# gesamt.net
KiCad netlist of a schematic drawn in EAGLE
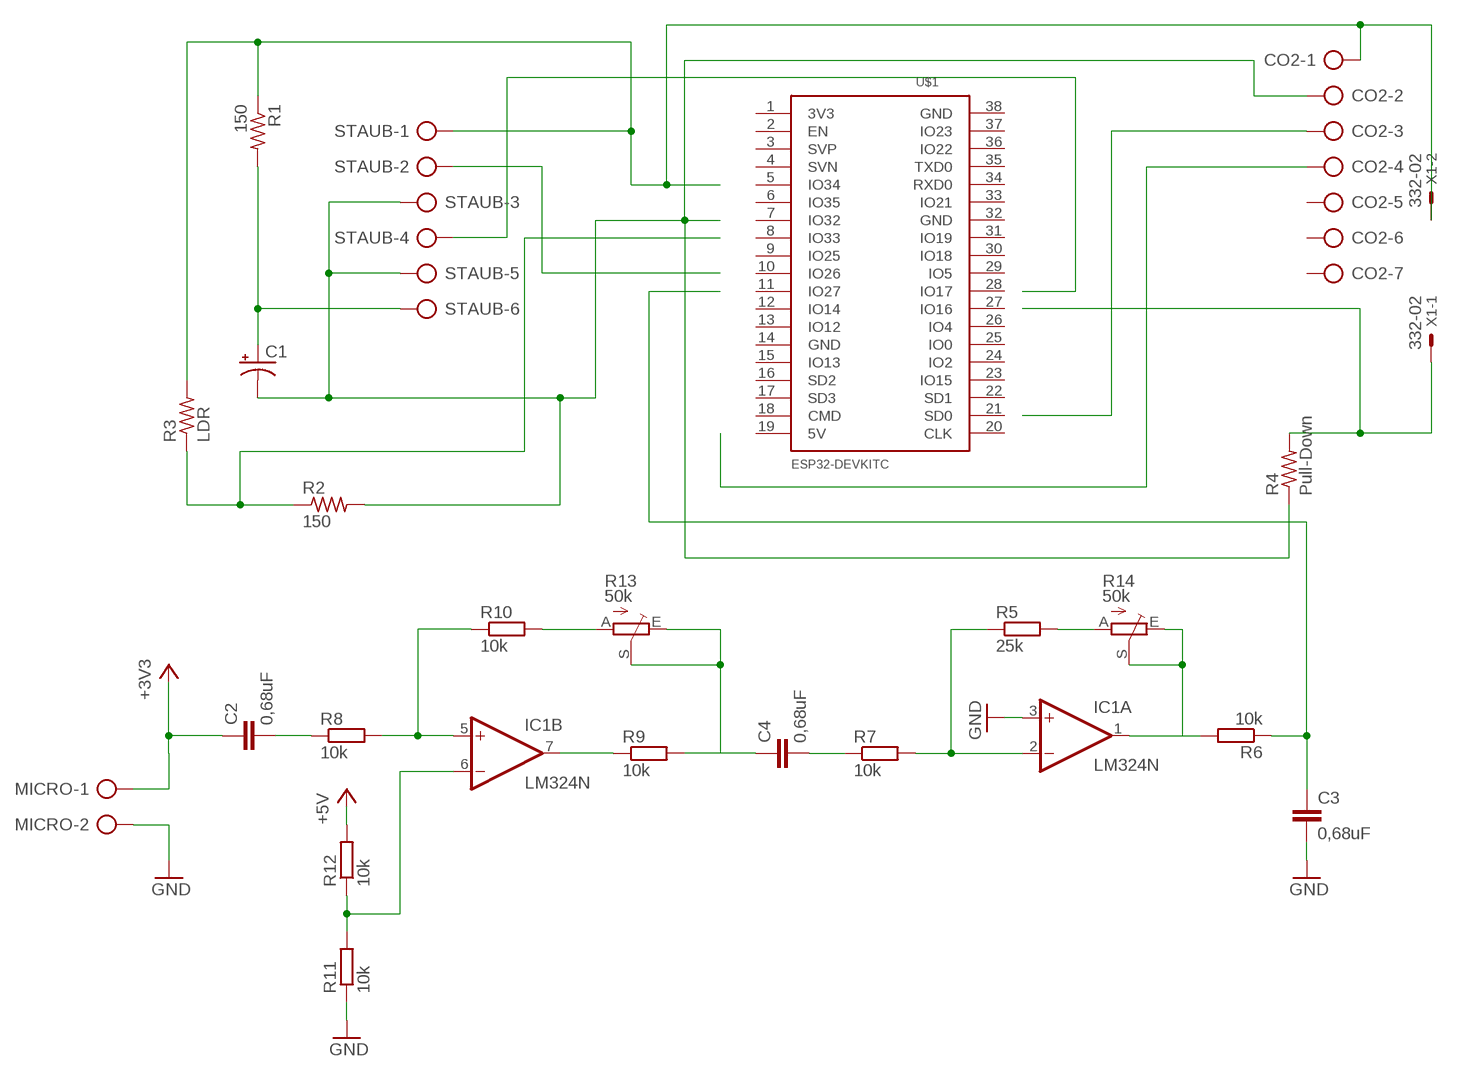
[diagram p0: schematic, sheet 1]

(export (version "E")
  (design (tool "Eeschema 10.0.6"))
  (components
    (comp (ref "C1")
      (value "CPOL-USE2,5-6E")
      (footprint "eagle-import:E2,5-6E")
      (libsource (lib "eagle-import") (part "CPOL-USE2,5-6E"))
    )
    (comp (ref "C2")
      (value "0,68uF")
      (footprint "eagle-import:C025-025X050")
      (libsource (lib "eagle-import") (part "C-EU025-025X050"))
    )
    (comp (ref "C3")
      (value "0,68uF")
      (footprint "eagle-import:C025-025X050")
      (libsource (lib "eagle-import") (part "C-EU025-025X050"))
    )
    (comp (ref "C4")
      (value "0,68uF")
      (footprint "eagle-import:C025-025X050")
      (libsource (lib "eagle-import") (part "C-EU025-025X050"))
    )
    (comp (ref "CO2")
      (value "AK300/7")
      (footprint "eagle-import:AK300_7")
      (libsource (lib "eagle-import") (part "AK300/7"))
    )
    (comp (ref "IC1")
      (value "LM324N")
      (footprint "eagle-import:DIL14")
      (libsource (lib "eagle-import") (part "LM324N"))
    )
    (comp (ref "MICRO")
      (value "AK300/2")
      (footprint "eagle-import:AK300_2")
      (libsource (lib "eagle-import") (part "AK300/2"))
    )
    (comp (ref "R1")
      (value "150")
      (footprint "eagle-import:0207_10")
      (libsource (lib "eagle-import") (part "R-US_0207/10"))
    )
    (comp (ref "R2")
      (value "150")
      (footprint "eagle-import:0207_10")
      (libsource (lib "eagle-import") (part "R-US_0207/10"))
    )
    (comp (ref "R3")
      (value "LDR")
      (footprint "eagle-import:V234_12")
      (libsource (lib "eagle-import") (part "R-US_V234/12"))
    )
    (comp (ref "R4")
      (value "Pull-Down")
      (footprint "eagle-import:0207_10")
      (libsource (lib "eagle-import") (part "R-US_0207/10"))
    )
    (comp (ref "R5")
      (value "25k")
      (footprint "eagle-import:0204_7")
      (libsource (lib "eagle-import") (part "R-EU_0204/7"))
    )
    (comp (ref "R6")
      (value "10k")
      (footprint "eagle-import:0204_7")
      (libsource (lib "eagle-import") (part "R-EU_0204/7"))
    )
    (comp (ref "R7")
      (value "10k")
      (footprint "eagle-import:0204_7")
      (libsource (lib "eagle-import") (part "R-EU_0204/7"))
    )
    (comp (ref "R8")
      (value "10k")
      (footprint "eagle-import:0204_7")
      (libsource (lib "eagle-import") (part "R-EU_0204/7"))
    )
    (comp (ref "R9")
      (value "10k")
      (footprint "eagle-import:0204_7")
      (libsource (lib "eagle-import") (part "R-EU_0204/7"))
    )
    (comp (ref "R10")
      (value "10k")
      (footprint "eagle-import:0204_7")
      (libsource (lib "eagle-import") (part "R-EU_0204/7"))
    )
    (comp (ref "R11")
      (value "10k")
      (footprint "eagle-import:0204_7")
      (libsource (lib "eagle-import") (part "R-EU_0204/7"))
    )
    (comp (ref "R12")
      (value "10k")
      (footprint "eagle-import:0204_7")
      (libsource (lib "eagle-import") (part "R-EU_0204/7"))
    )
    (comp (ref "R13")
      (value "50k")
      (footprint "eagle-import:LI10")
      (libsource (lib "eagle-import") (part "TRIM_EU-LI10"))
    )
    (comp (ref "R14")
      (value "50k")
      (footprint "eagle-import:LI10")
      (libsource (lib "eagle-import") (part "TRIM_EU-LI10"))
    )
    (comp (ref "STAUB")
      (value "AK300/6")
      (footprint "eagle-import:AK300_6")
      (libsource (lib "eagle-import") (part "AK300/6"))
    )
    (comp (ref "U$1")
      (value "ESP32DEVKITC")
      (footprint "eagle-import:ESP32-DEVKITC")
      (libsource (lib "eagle-import") (part "ESP32DEVKITC"))
    )
    (comp (ref "X1")
      (value "332-02")
      (footprint "eagle-import:332-02")
      (libsource (lib "eagle-import") (part "332-02"))
    )
  )
  (nets
    (net (code "1") (name "+3V3") (class "Default")
      (node (ref "C2") (pin "1") (pinfunction "1_1") (pintype "passive"))
      (node (ref "MICRO") (pin "1") (pinfunction "KL_1") (pintype "passive"))
    )
    (net (code "2") (name "+5V") (class "Default")
      (node (ref "R12") (pin "2") (pinfunction "2_2") (pintype "passive"))
    )
    (net (code "3") (name "GND") (class "Default")
      (node (ref "C3") (pin "2") (pinfunction "2_2") (pintype "passive"))
      (node (ref "IC1") (pin "3") (pinfunction "+IN_3") (pintype "input"))
      (node (ref "MICRO") (pin "2") (pinfunction "KL_2") (pintype "passive"))
      (node (ref "R11") (pin "1") (pinfunction "1_1") (pintype "passive"))
    )
    (net (code "4") (name "Net-(C2-Pad2)") (class "Default")
      (node (ref "C2") (pin "2") (pinfunction "2_2") (pintype "passive"))
      (node (ref "R8") (pin "1") (pinfunction "1_1") (pintype "passive"))
    )
    (net (code "5") (name "Net-(C3-Pad1)") (class "Default")
      (node (ref "C3") (pin "1") (pinfunction "1_1") (pintype "passive"))
      (node (ref "R6") (pin "1") (pinfunction "1_1") (pintype "passive"))
    )
    (net (code "6") (name "Net-(C4-Pad1)") (class "Default")
      (node (ref "C4") (pin "1") (pinfunction "1_1") (pintype "passive"))
      (node (ref "R13") (pin "E") (pinfunction "E_E") (pintype "passive"))
      (node (ref "R13") (pin "S") (pinfunction "S_S") (pintype "passive"))
      (node (ref "R9") (pin "2") (pinfunction "2_2") (pintype "passive"))
    )
    (net (code "7") (name "Net-(C4-Pad2)") (class "Default")
      (node (ref "C4") (pin "2") (pinfunction "2_2") (pintype "passive"))
      (node (ref "R7") (pin "1") (pinfunction "1_1") (pintype "passive"))
    )
    (net (code "8") (name "Net-(CO2A-KL)") (class "Default")
      (node (ref "CO2") (pin "1") (pinfunction "KL_1") (pintype "passive"))
      (node (ref "R1") (pin "1") (pinfunction "1_1") (pintype "passive"))
      (node (ref "R3") (pin "2") (pinfunction "2_2") (pintype "passive"))
      (node (ref "STAUB") (pin "1") (pinfunction "KL_1") (pintype "passive"))
      (node (ref "X1") (pin "2") (pinfunction "S_2") (pintype "passive"))
    )
    (net (code "9") (name "Net-(CO2B-KL)") (class "Default")
      (node (ref "C1") (pin "-") (pinfunction "-_-") (pintype "passive"))
      (node (ref "CO2") (pin "2") (pinfunction "KL_2") (pintype "passive"))
      (node (ref "R2") (pin "2") (pinfunction "2_2") (pintype "passive"))
      (node (ref "R4") (pin "1") (pinfunction "1_1") (pintype "passive"))
      (node (ref "STAUB") (pin "3") (pinfunction "KL_3") (pintype "passive"))
      (node (ref "STAUB") (pin "5") (pinfunction "KL_5") (pintype "passive"))
    )
    (net (code "10") (name "Net-(IC1A--IN)") (class "Default")
      (node (ref "IC1") (pin "2") (pinfunction "-IN_2") (pintype "input"))
      (node (ref "R5") (pin "1") (pinfunction "1_1") (pintype "passive"))
      (node (ref "R7") (pin "2") (pinfunction "2_2") (pintype "passive"))
    )
    (net (code "11") (name "Net-(IC1A-OUT)") (class "Default")
      (node (ref "IC1") (pin "1") (pinfunction "OUT_1") (pintype "output"))
      (node (ref "R14") (pin "E") (pinfunction "E_E") (pintype "passive"))
      (node (ref "R14") (pin "S") (pinfunction "S_S") (pintype "passive"))
      (node (ref "R6") (pin "2") (pinfunction "2_2") (pintype "passive"))
    )
    (net (code "12") (name "Net-(IC1B-+IN)") (class "Default")
      (node (ref "IC1") (pin "5") (pinfunction "+IN_5") (pintype "input"))
      (node (ref "R10") (pin "1") (pinfunction "1_1") (pintype "passive"))
      (node (ref "R8") (pin "2") (pinfunction "2_2") (pintype "passive"))
    )
    (net (code "13") (name "Net-(IC1B--IN)") (class "Default")
      (node (ref "IC1") (pin "6") (pinfunction "-IN_6") (pintype "input"))
      (node (ref "R11") (pin "2") (pinfunction "2_2") (pintype "passive"))
      (node (ref "R12") (pin "1") (pinfunction "1_1") (pintype "passive"))
    )
    (net (code "14") (name "Net-(IC1B-OUT)") (class "Default")
      (node (ref "IC1") (pin "7") (pinfunction "OUT_7") (pintype "output"))
      (node (ref "R9") (pin "1") (pinfunction "1_1") (pintype "passive"))
    )
    (net (code "15") (name "Net-(R2-Pad1)") (class "Default")
      (node (ref "R2") (pin "1") (pinfunction "1_1") (pintype "passive"))
      (node (ref "R3") (pin "1") (pinfunction "1_1") (pintype "passive"))
    )
    (net (code "16") (name "Net-(R10-Pad2)") (class "Default")
      (node (ref "R10") (pin "2") (pinfunction "2_2") (pintype "passive"))
      (node (ref "R13") (pin "A") (pinfunction "A_A") (pintype "passive"))
    )
    (net (code "17") (name "Net-(R14-PadA)") (class "Default")
      (node (ref "R14") (pin "A") (pinfunction "A_A") (pintype "passive"))
      (node (ref "R5") (pin "2") (pinfunction "2_2") (pintype "passive"))
    )
    (net (code "18") (name "Net-(STAUBF-KL)") (class "Default")
      (node (ref "C1") (pin "+") (pinfunction "+_+") (pintype "passive"))
      (node (ref "R1") (pin "2") (pinfunction "2_2") (pintype "passive"))
      (node (ref "STAUB") (pin "6") (pinfunction "KL_6") (pintype "passive"))
    )
    (net (code "19") (name "Net-(X1A-S)") (class "Default")
      (node (ref "R4") (pin "2") (pinfunction "2_2") (pintype "passive"))
      (node (ref "X1") (pin "1") (pinfunction "S_1") (pintype "passive"))
    )
    (net (code "20") (name "unconnected-(CO2C-KL-Pad3)") (class "Default")
      (node (ref "CO2") (pin "3") (pinfunction "KL_3") (pintype "passive"))
    )
    (net (code "21") (name "unconnected-(CO2D-KL-Pad4)") (class "Default")
      (node (ref "CO2") (pin "4") (pinfunction "KL_4") (pintype "passive"))
    )
    (net (code "22") (name "unconnected-(CO2E-KL-Pad5)") (class "Default")
      (node (ref "CO2") (pin "5") (pinfunction "KL_5") (pintype "passive"))
    )
    (net (code "23") (name "unconnected-(CO2F-KL-Pad6)") (class "Default")
      (node (ref "CO2") (pin "6") (pinfunction "KL_6") (pintype "passive"))
    )
    (net (code "24") (name "unconnected-(CO2G-KL-Pad7)") (class "Default")
      (node (ref "CO2") (pin "7") (pinfunction "KL_7") (pintype "passive"))
    )
    (net (code "25") (name "unconnected-(STAUBB-KL-Pad2)") (class "Default")
      (node (ref "STAUB") (pin "2") (pinfunction "KL_2") (pintype "passive"))
    )
    (net (code "26") (name "unconnected-(STAUBD-KL-Pad4)") (class "Default")
      (node (ref "STAUB") (pin "4") (pinfunction "KL_4") (pintype "passive"))
    )
    (net (code "27") (name "unconnected-(U$1-3V3-Pad1)") (class "Default")
      (node (ref "U$1") (pin "1") (pinfunction "3V3_1") (pintype "bidirectional"))
    )
    (net (code "28") (name "unconnected-(U$1-5V-Pad19)") (class "Default")
      (node (ref "U$1") (pin "19") (pinfunction "5V_19") (pintype "bidirectional"))
    )
    (net (code "29") (name "unconnected-(U$1-CLK-Pad20)") (class "Default")
      (node (ref "U$1") (pin "20") (pinfunction "CLK_20") (pintype "bidirectional"))
    )
    (net (code "30") (name "unconnected-(U$1-CMD-Pad18)") (class "Default")
      (node (ref "U$1") (pin "18") (pinfunction "CMD_18") (pintype "bidirectional"))
    )
    (net (code "31") (name "unconnected-(U$1-EN-Pad2)") (class "Default")
      (node (ref "U$1") (pin "2") (pinfunction "EN_2") (pintype "bidirectional"))
    )
    (net (code "32") (name "unconnected-(U$1-GND-Pad14)") (class "Default")
      (node (ref "U$1") (pin "14") (pinfunction "GND_14") (pintype "bidirectional"))
    )
    (net (code "33") (name "unconnected-(U$1-GND-Pad32)") (class "Default")
      (node (ref "U$1") (pin "32") (pinfunction "GND_32") (pintype "bidirectional"))
    )
    (net (code "34") (name "unconnected-(U$1-GND-Pad38)") (class "Default")
      (node (ref "U$1") (pin "38") (pinfunction "GND_38") (pintype "bidirectional"))
    )
    (net (code "35") (name "unconnected-(U$1-IO0-Pad25)") (class "Default")
      (node (ref "U$1") (pin "25") (pinfunction "IO0_25") (pintype "bidirectional"))
    )
    (net (code "36") (name "unconnected-(U$1-IO2-Pad24)") (class "Default")
      (node (ref "U$1") (pin "24") (pinfunction "IO2_24") (pintype "bidirectional"))
    )
    (net (code "37") (name "unconnected-(U$1-IO4-Pad26)") (class "Default")
      (node (ref "U$1") (pin "26") (pinfunction "IO4_26") (pintype "bidirectional"))
    )
    (net (code "38") (name "unconnected-(U$1-IO5-Pad29)") (class "Default")
      (node (ref "U$1") (pin "29") (pinfunction "IO5_29") (pintype "bidirectional"))
    )
    (net (code "39") (name "unconnected-(U$1-IO12-Pad13)") (class "Default")
      (node (ref "U$1") (pin "13") (pinfunction "IO12_13") (pintype "bidirectional"))
    )
    (net (code "40") (name "unconnected-(U$1-IO13-Pad15)") (class "Default")
      (node (ref "U$1") (pin "15") (pinfunction "IO13_15") (pintype "bidirectional"))
    )
    (net (code "41") (name "unconnected-(U$1-IO14-Pad12)") (class "Default")
      (node (ref "U$1") (pin "12") (pinfunction "IO14_12") (pintype "bidirectional"))
    )
    (net (code "42") (name "unconnected-(U$1-IO15-Pad23)") (class "Default")
      (node (ref "U$1") (pin "23") (pinfunction "IO15_23") (pintype "bidirectional"))
    )
    (net (code "43") (name "unconnected-(U$1-IO16-Pad27)") (class "Default")
      (node (ref "U$1") (pin "27") (pinfunction "IO16_27") (pintype "bidirectional"))
    )
    (net (code "44") (name "unconnected-(U$1-IO17-Pad28)") (class "Default")
      (node (ref "U$1") (pin "28") (pinfunction "IO17_28") (pintype "bidirectional"))
    )
    (net (code "45") (name "unconnected-(U$1-IO18-Pad30)") (class "Default")
      (node (ref "U$1") (pin "30") (pinfunction "IO18_30") (pintype "bidirectional"))
    )
    (net (code "46") (name "unconnected-(U$1-IO19-Pad31)") (class "Default")
      (node (ref "U$1") (pin "31") (pinfunction "IO19_31") (pintype "bidirectional"))
    )
    (net (code "47") (name "unconnected-(U$1-IO21-Pad33)") (class "Default")
      (node (ref "U$1") (pin "33") (pinfunction "IO21_33") (pintype "bidirectional"))
    )
    (net (code "48") (name "unconnected-(U$1-IO22-Pad36)") (class "Default")
      (node (ref "U$1") (pin "36") (pinfunction "IO22_36") (pintype "bidirectional"))
    )
    (net (code "49") (name "unconnected-(U$1-IO23-Pad37)") (class "Default")
      (node (ref "U$1") (pin "37") (pinfunction "IO23_37") (pintype "bidirectional"))
    )
    (net (code "50") (name "unconnected-(U$1-IO25-Pad9)") (class "Default")
      (node (ref "U$1") (pin "9") (pinfunction "IO25_9") (pintype "bidirectional"))
    )
    (net (code "51") (name "unconnected-(U$1-IO26-Pad10)") (class "Default")
      (node (ref "U$1") (pin "10") (pinfunction "IO26_10") (pintype "bidirectional"))
    )
    (net (code "52") (name "unconnected-(U$1-IO27-Pad11)") (class "Default")
      (node (ref "U$1") (pin "11") (pinfunction "IO27_11") (pintype "bidirectional"))
    )
    (net (code "53") (name "unconnected-(U$1-IO32-Pad7)") (class "Default")
      (node (ref "U$1") (pin "7") (pinfunction "IO32_7") (pintype "bidirectional"))
    )
    (net (code "54") (name "unconnected-(U$1-IO33-Pad8)") (class "Default")
      (node (ref "U$1") (pin "8") (pinfunction "IO33_8") (pintype "bidirectional"))
    )
    (net (code "55") (name "unconnected-(U$1-IO34-Pad5)") (class "Default")
      (node (ref "U$1") (pin "5") (pinfunction "IO34_5") (pintype "bidirectional"))
    )
    (net (code "56") (name "unconnected-(U$1-IO35-Pad6)") (class "Default")
      (node (ref "U$1") (pin "6") (pinfunction "IO35_6") (pintype "bidirectional"))
    )
    (net (code "57") (name "unconnected-(U$1-RXD0-Pad34)") (class "Default")
      (node (ref "U$1") (pin "34") (pinfunction "RXD0_34") (pintype "bidirectional"))
    )
    (net (code "58") (name "unconnected-(U$1-SD0-Pad21)") (class "Default")
      (node (ref "U$1") (pin "21") (pinfunction "SD0_21") (pintype "bidirectional"))
    )
    (net (code "59") (name "unconnected-(U$1-SD1-Pad22)") (class "Default")
      (node (ref "U$1") (pin "22") (pinfunction "SD1_22") (pintype "bidirectional"))
    )
    (net (code "60") (name "unconnected-(U$1-SD2-Pad16)") (class "Default")
      (node (ref "U$1") (pin "16") (pinfunction "SD2_16") (pintype "bidirectional"))
    )
    (net (code "61") (name "unconnected-(U$1-SD3-Pad17)") (class "Default")
      (node (ref "U$1") (pin "17") (pinfunction "SD3_17") (pintype "bidirectional"))
    )
    (net (code "62") (name "unconnected-(U$1-SVN-Pad4)") (class "Default")
      (node (ref "U$1") (pin "4") (pinfunction "SVN_4") (pintype "bidirectional"))
    )
    (net (code "63") (name "unconnected-(U$1-SVP-Pad3)") (class "Default")
      (node (ref "U$1") (pin "3") (pinfunction "SVP_3") (pintype "bidirectional"))
    )
    (net (code "64") (name "unconnected-(U$1-TXD0-Pad35)") (class "Default")
      (node (ref "U$1") (pin "35") (pinfunction "TXD0_35") (pintype "bidirectional"))
    )
  )
)
